# schematic.net
KiCad netlist of a schematic drawn in EasyEDA
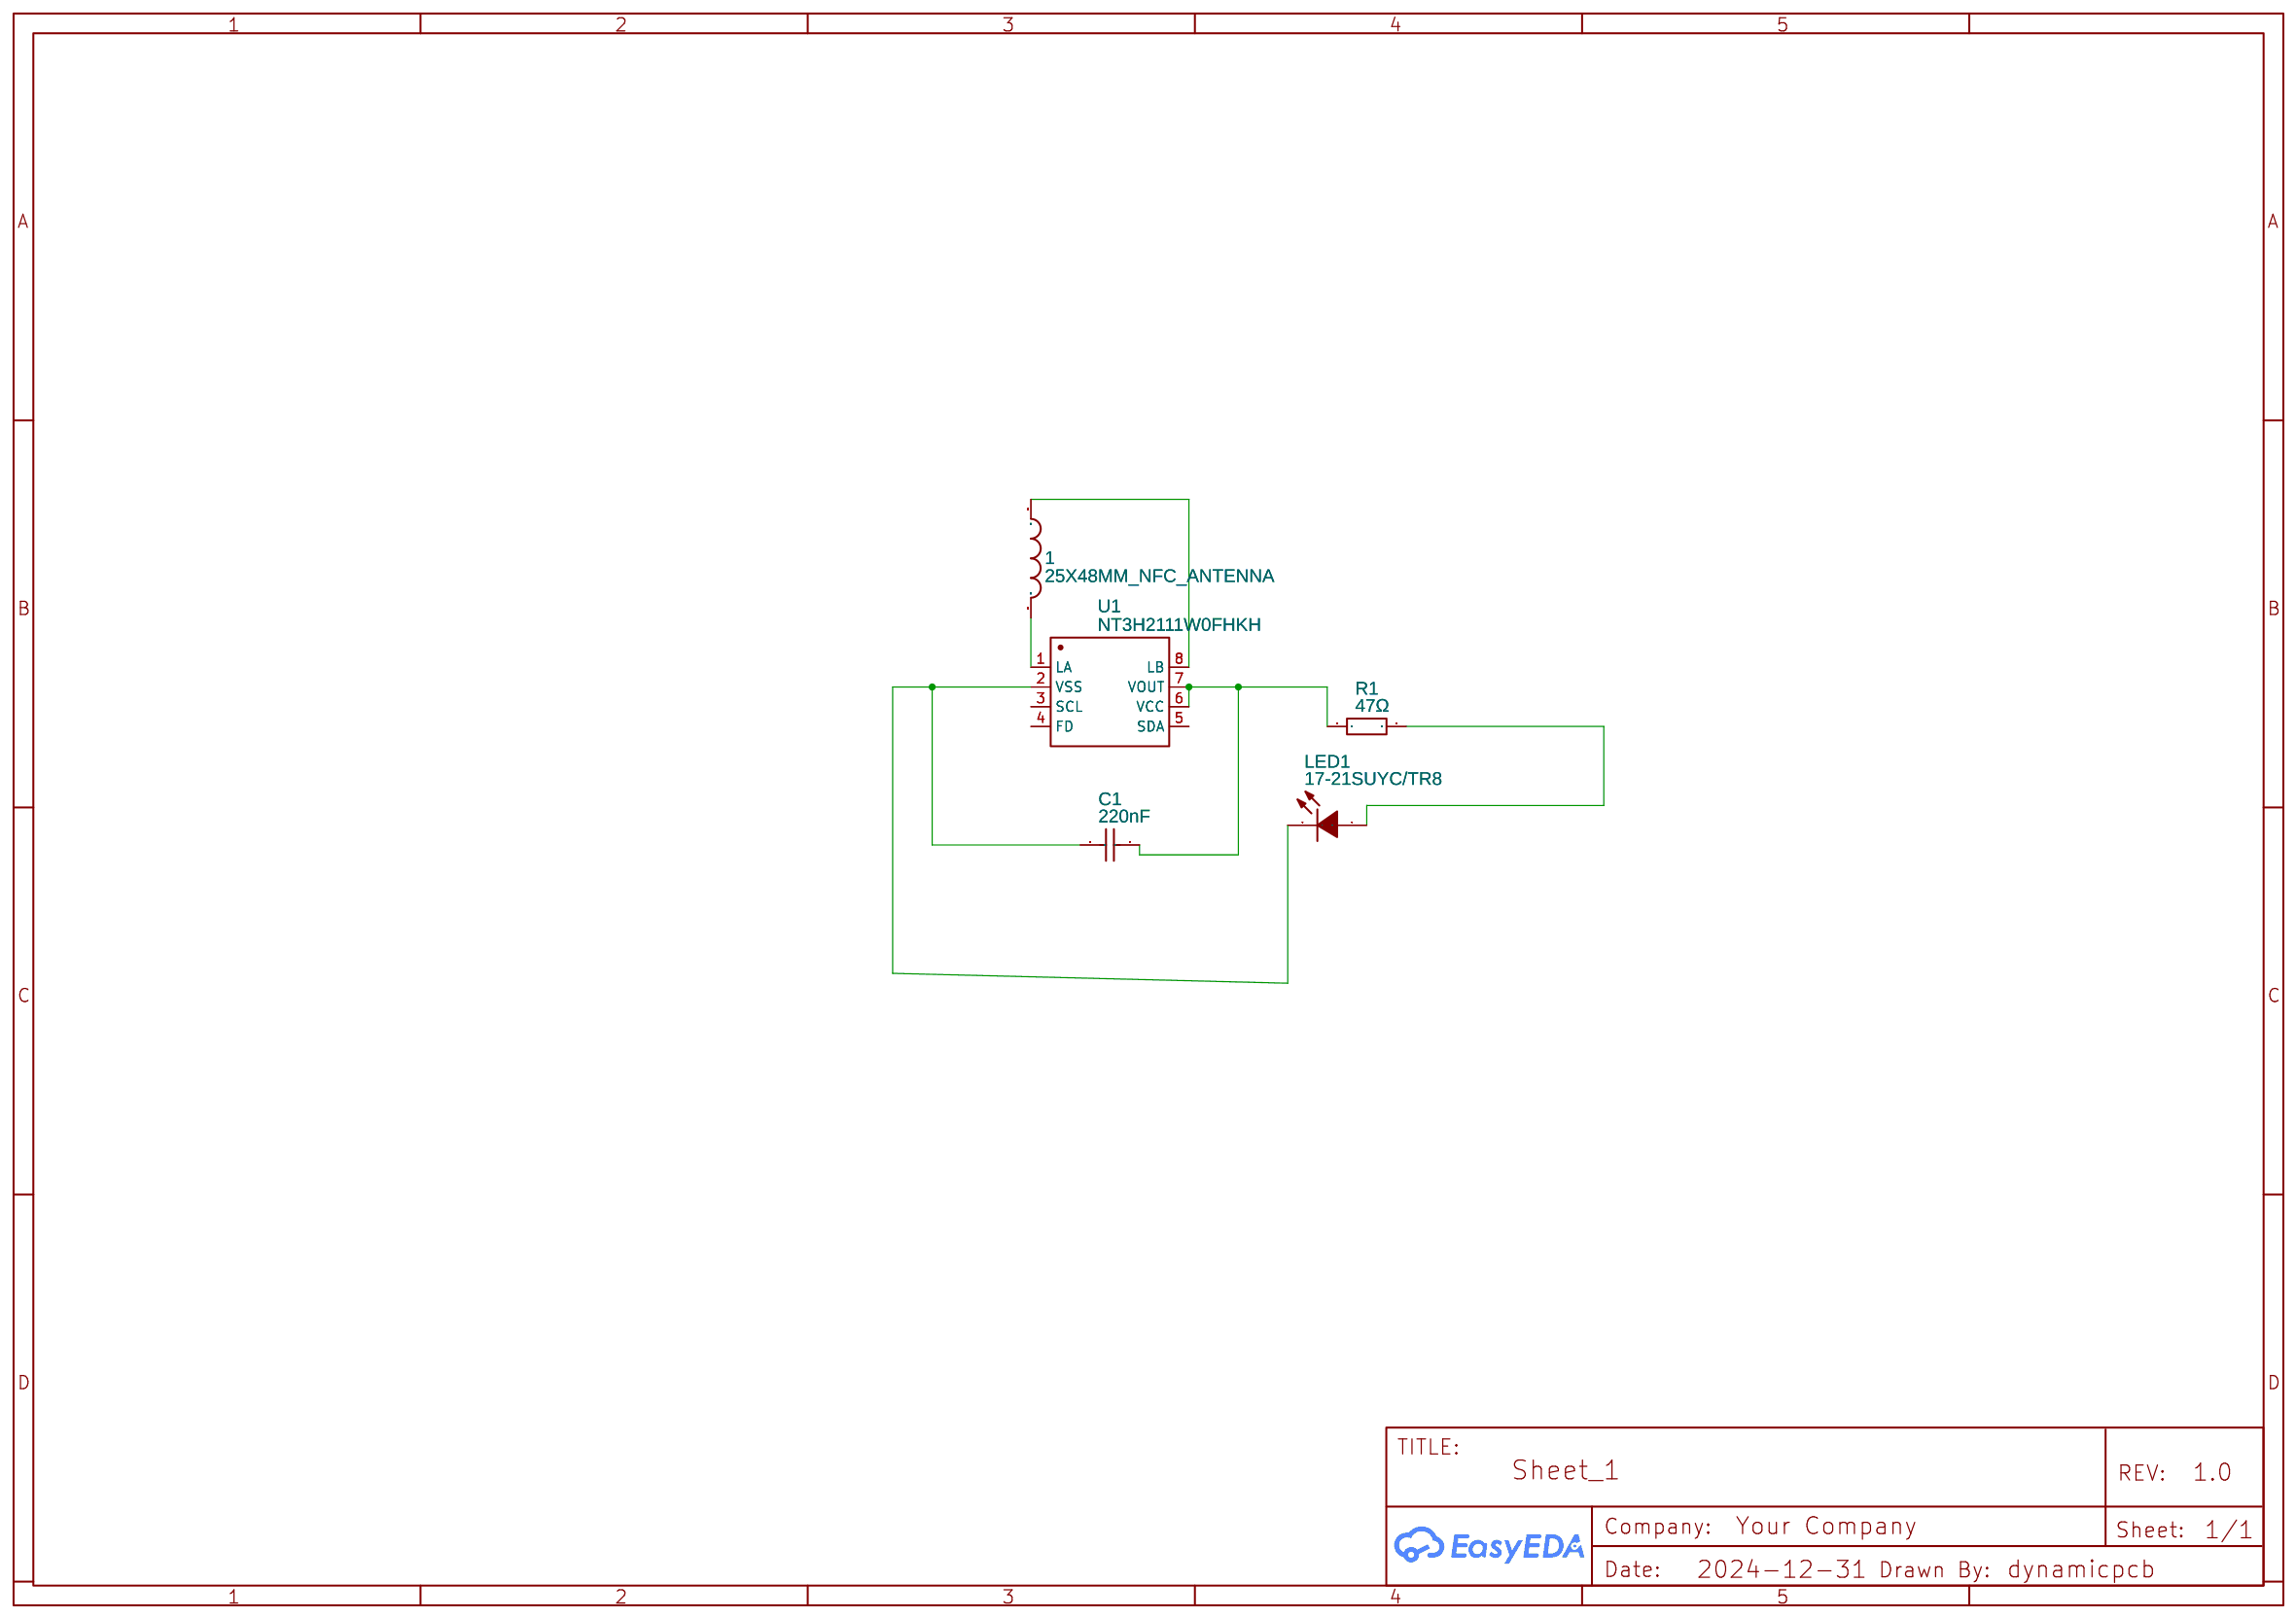
[diagram p0: schematic sheet]

(export (version "E")
  (design (tool "Eeschema 10.0.6"))
  (components
    (comp (ref "1") (value "25X48MM_NFC_ANTENNA") (libsource (lib "") (part "25X48MM_NFC_ANTENNA")))
    (comp (ref "C1")
      (value "220nF")
      (fields
        (field (name "Manufacturer Part") "CL10B224KA8NNNC")
        (field (name "Manufacturer") "SAMSUNG(三星)")
      )
      (libsource (lib "") (part "CL10B224KA8NNNC"))
    )
    (comp (ref "LED1")
      (value "17-21SUYC/TR8")
      (fields (field (name "Manufacturer Part") "KT-0805黄灯") (field (name "Manufacturer") "KENTO"))
      (libsource (lib "") (part "17-21SUYC/TR8"))
    )
    (comp (ref "R1")
      (value "47Ω")
      (fields
        (field (name "Manufacturer Part") "0603WAF470JT5E")
        (field (name "Manufacturer") "UNI-ROYAL(厚声)")
      )
      (libsource (lib "") (part "0603WAF470JT5E"))
    )
    (comp (ref "U1")
      (value "NT3H2111W0FHKH")
      (fields (field (name "Manufacturer") "NXP(恩智浦)"))
      (libsource (lib "") (part "NT3H2111W0FHKH"))
    )
  )
  (nets
    (net (code "1") (name "Net-(LED1-+)") (class "Default")
      (node (ref "LED1") (pin "1") (pinfunction "+_1") (pintype "unspecified"))
      (node (ref "R1") (pin "2") (pinfunction "2_2") (pintype "input"))
    )
    (net (code "2") (name "Net-(LED1--)") (class "Default")
      (node (ref "C1") (pin "1") (pinfunction "1_1") (pintype "input"))
      (node (ref "LED1") (pin "2") (pinfunction "-_2") (pintype "unspecified"))
      (node (ref "U1") (pin "2") (pinfunction "VSS_2") (pintype "unspecified"))
    )
    (net (code "3") (name "Net-(U1-LA)") (class "Default")
      (node (ref "1") (pin "P$2") (pinfunction "P$2_P$2") (pintype "bidirectional"))
      (node (ref "U1") (pin "1") (pinfunction "LA_1") (pintype "unspecified"))
    )
    (net (code "4") (name "Net-(U1-LB)") (class "Default")
      (node (ref "1") (pin "P$1") (pinfunction "P$1_P$1") (pintype "bidirectional"))
      (node (ref "U1") (pin "8") (pinfunction "LB_8") (pintype "unspecified"))
    )
    (net (code "5") (name "Net-(U1-VCC)") (class "Default")
      (node (ref "C1") (pin "2") (pinfunction "2_2") (pintype "input"))
      (node (ref "R1") (pin "1") (pinfunction "1_1") (pintype "input"))
      (node (ref "U1") (pin "6") (pinfunction "VCC_6") (pintype "unspecified"))
      (node (ref "U1") (pin "7") (pinfunction "VOUT_7") (pintype "unspecified"))
    )
    (net (code "6") (name "unconnected-(U1-FD-Pad4)") (class "Default")
      (node (ref "U1") (pin "4") (pinfunction "FD_4") (pintype "unspecified"))
    )
    (net (code "7") (name "unconnected-(U1-SCL-Pad3)") (class "Default")
      (node (ref "U1") (pin "3") (pinfunction "SCL_3") (pintype "unspecified"))
    )
    (net (code "8") (name "unconnected-(U1-SDA-Pad5)") (class "Default")
      (node (ref "U1") (pin "5") (pinfunction "SDA_5") (pintype "unspecified"))
    )
  )
)
